# design.net
KiCad netlist of a schematic drawn in Altium Designer
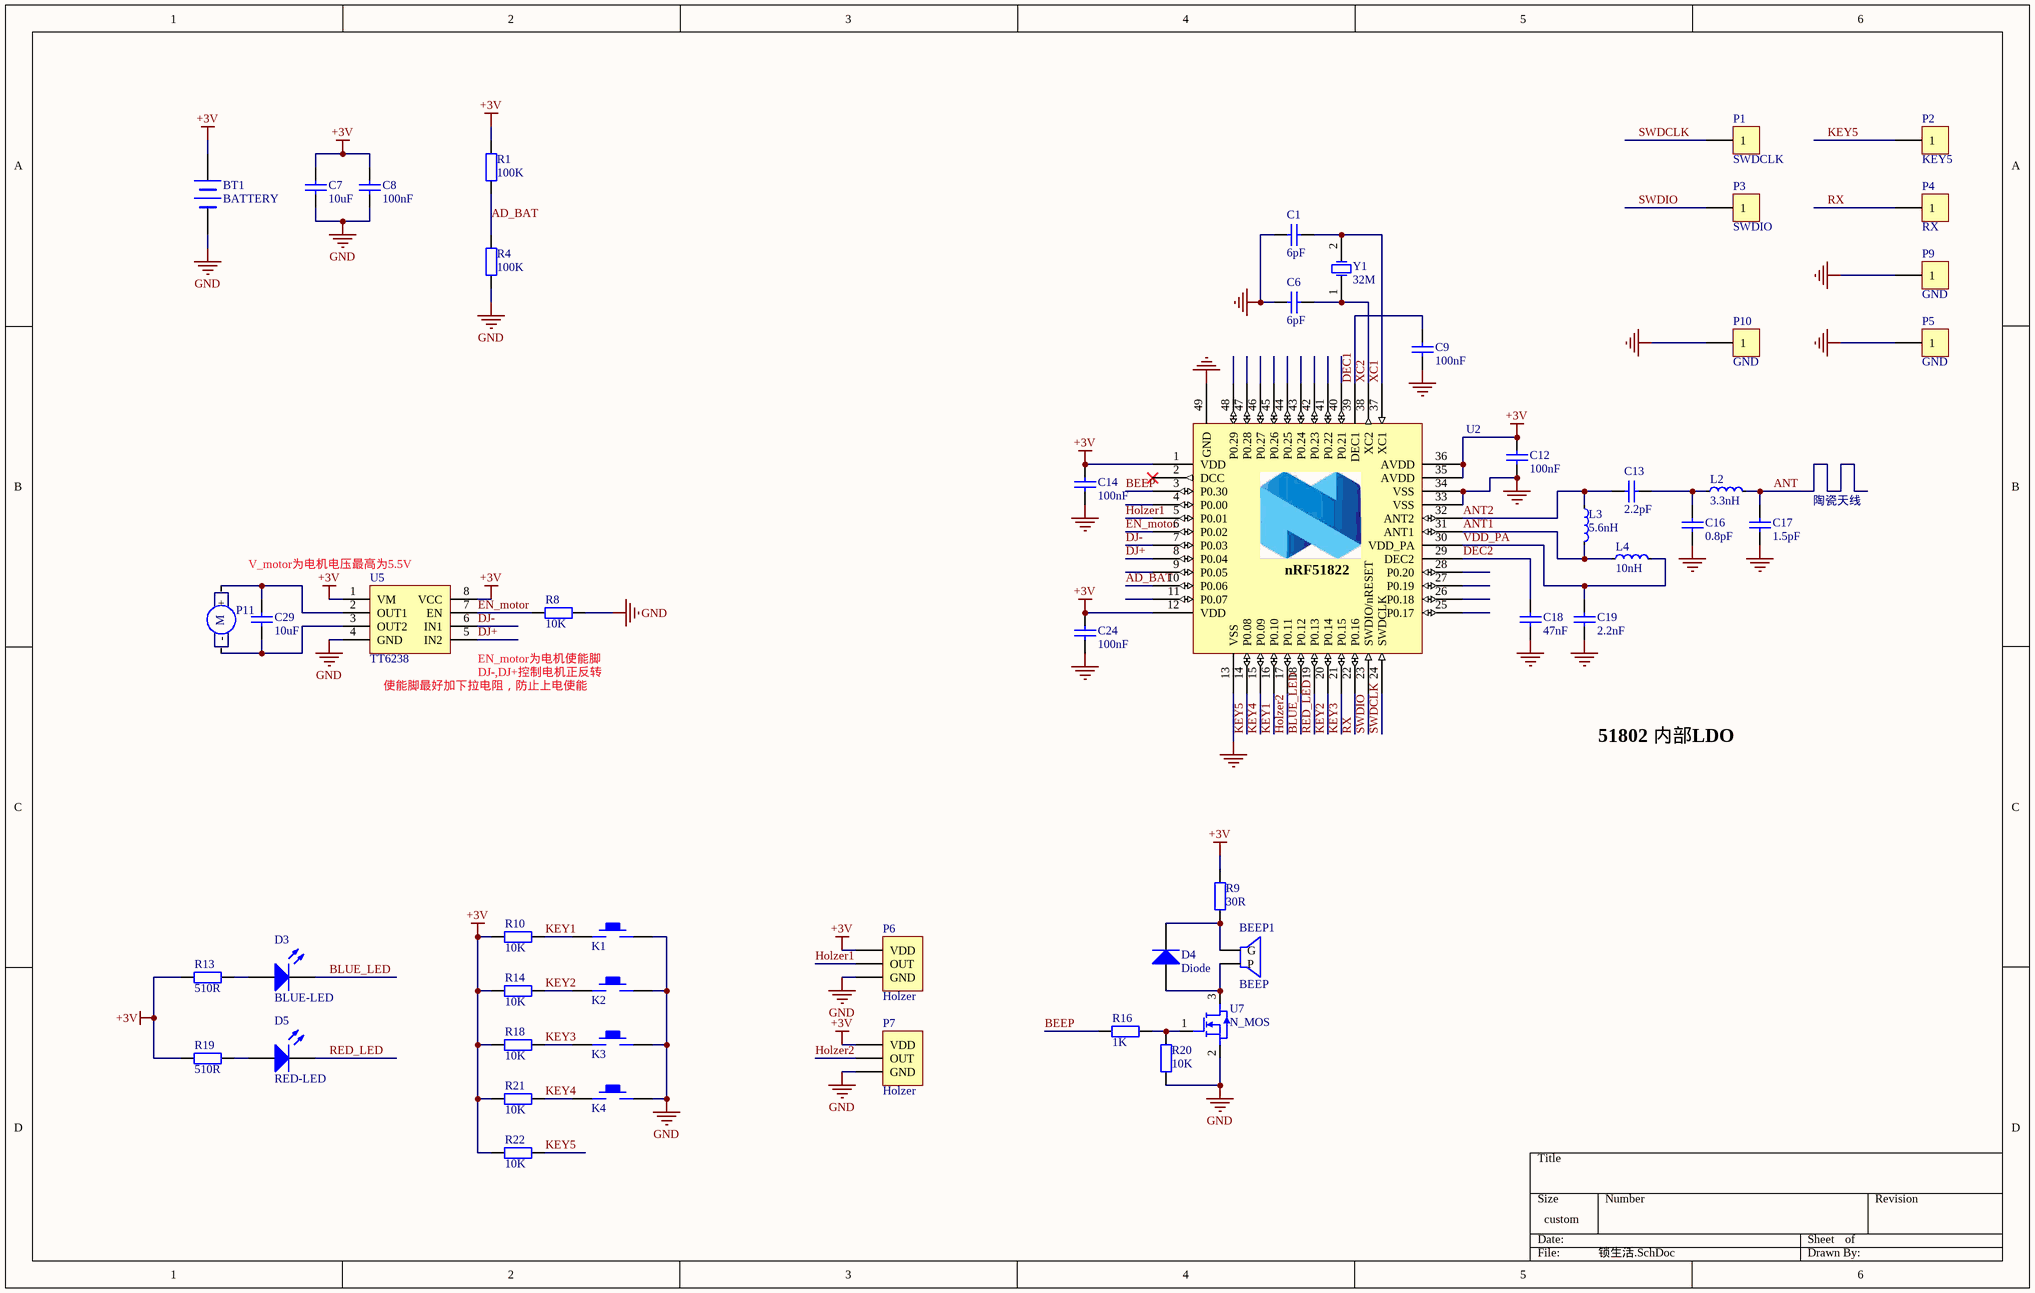
[diagram p0: 锁生活.SchDoc]

(export (version "E")
  (design (tool "Eeschema 10.0.6"))
  (components
    (comp (ref "BEEP1")
      (value "BEEP")
      (footprint "BELL-φ5")
      (description "蜂鸣器")
      (libsource (lib "常用集成库") (part "BEEP"))
    )
    (comp (ref "BT1")
      (value "BATTERY")
      (footprint "2P-1.0卧贴连接器")
      (description "电池")
      (libsource (lib "常用集成库") (part "BATTERY"))
    )
    (comp (ref "C1")
      (value "6pF")
      (footprint "0402_C")
      (description "Capacitor")
      (fields (field (name "PUBLISHER") "Altium Limited"))
      (libsource (lib "常用集成库") (part "Cap"))
    )
    (comp (ref "C6")
      (value "6pF")
      (footprint "0402_C")
      (description "Capacitor")
      (fields (field (name "PUBLISHER") "Altium Limited"))
      (libsource (lib "常用集成库") (part "Cap"))
    )
    (comp (ref "C7")
      (value "10uF")
      (footprint "0402_C")
      (description "Capacitor")
      (fields (field (name "PUBLISHER") "Altium Limited"))
      (libsource (lib "常用集成库") (part "Cap"))
    )
    (comp (ref "C8")
      (value "100nF")
      (footprint "0402_C")
      (description "Capacitor")
      (fields (field (name "PUBLISHER") "Altium Limited"))
      (libsource (lib "常用集成库") (part "Cap"))
    )
    (comp (ref "C9")
      (value "100nF")
      (footprint "0402_C")
      (description "Capacitor")
      (fields (field (name "PUBLISHER") "Altium Limited"))
      (libsource (lib "常用集成库") (part "Cap"))
    )
    (comp (ref "C12")
      (value "100nF")
      (footprint "0402_C")
      (description "Capacitor")
      (fields (field (name "PUBLISHER") "Altium Limited"))
      (libsource (lib "常用集成库") (part "Cap"))
    )
    (comp (ref "C13")
      (value "2.2pF")
      (footprint "0402_C")
      (description "Capacitor")
      (fields (field (name "PUBLISHER") "Altium Limited"))
      (libsource (lib "常用集成库") (part "Cap"))
    )
    (comp (ref "C14")
      (value "100nF")
      (footprint "0402_C")
      (description "Capacitor")
      (fields (field (name "PUBLISHER") "Altium Limited"))
      (libsource (lib "常用集成库") (part "Cap"))
    )
    (comp (ref "C16")
      (value "0.8pF")
      (footprint "0402_C")
      (description "Capacitor")
      (fields (field (name "PUBLISHER") "Altium Limited"))
      (libsource (lib "常用集成库") (part "Cap"))
    )
    (comp (ref "C17")
      (value "1.5pF")
      (footprint "0402_C")
      (description "Capacitor")
      (fields (field (name "PUBLISHER") "Altium Limited"))
      (libsource (lib "常用集成库") (part "Cap"))
    )
    (comp (ref "C18")
      (value "47nF")
      (footprint "0402_C")
      (description "Capacitor")
      (fields (field (name "PUBLISHER") "Altium Limited"))
      (libsource (lib "常用集成库") (part "Cap"))
    )
    (comp (ref "C19")
      (value "2.2nF")
      (footprint "0402_C")
      (description "Capacitor")
      (fields (field (name "PUBLISHER") "Altium Limited"))
      (libsource (lib "常用集成库") (part "Cap"))
    )
    (comp (ref "C24")
      (value "100nF")
      (footprint "0402_C")
      (description "Capacitor")
      (fields (field (name "PUBLISHER") "Altium Limited"))
      (libsource (lib "常用集成库") (part "Cap"))
    )
    (comp (ref "C29")
      (value "10uF")
      (footprint "LC-0402_C")
      (description "Capacitor")
      (fields (field (name "PUBLISHER") "Altium Limited"))
      (libsource (lib "MHLibrary") (part "Cap"))
    )
    (comp (ref "D3")
      (value "BLUE-LED")
      (footprint "0402_LED")
      (description "Typical RED, GREEN, YELLOW, AMBER GaAs LED")
      (fields (field (name "PUBLISHER") "Altium Limited"))
      (libsource (lib "常用集成库") (part "LED"))
    )
    (comp (ref "D4")
      (value "Diode")
      (footprint "SOD-123F")
      (description "diode")
      (fields (field (name "PUBLISHER") "Altium Limited"))
      (libsource (lib "常用集成库") (part "Diode"))
    )
    (comp (ref "D5")
      (value "RED-LED")
      (footprint "0402_LED")
      (description "Typical RED, GREEN, YELLOW, AMBER GaAs LED")
      (fields (field (name "PUBLISHER") "Altium Limited"))
      (libsource (lib "常用集成库") (part "LED"))
    )
    (comp (ref "K1") (value "KEY") (footprint "KEY_SMT4x4x1.5") (libsource (lib "常用集成库") (part "KEY")))
    (comp (ref "K2") (value "KEY") (footprint "KEY_SMT4x4x1.5") (libsource (lib "常用集成库") (part "KEY")))
    (comp (ref "K3") (value "KEY") (footprint "KEY_SMT4x4x1.5") (libsource (lib "常用集成库") (part "KEY")))
    (comp (ref "K4") (value "KEY") (footprint "KEY_SMT4x4x1.5") (libsource (lib "常用集成库") (part "KEY")))
    (comp (ref "L2") (value "3.3nH") (footprint "0402_L") (libsource (lib "常用集成库") (part "L")))
    (comp (ref "L3") (value "5.6nH") (footprint "0402_L") (libsource (lib "常用集成库") (part "L")))
    (comp (ref "L4") (value "10nH") (footprint "0402_L") (libsource (lib "常用集成库") (part "L")))
    (comp (ref "P1")
      (value "SWDCLK")
      (footprint "1P")
      (description "Header, 1-Pin")
      (fields (field (name "PUBLISHER") "Altium Limited"))
      (libsource (lib "常用集成库") (part "Header 1"))
    )
    (comp (ref "P2")
      (value "KEY5")
      (footprint "1P")
      (description "Header, 1-Pin")
      (fields (field (name "PUBLISHER") "Altium Limited"))
      (libsource (lib "常用集成库") (part "Header 1"))
    )
    (comp (ref "P3")
      (value "SWDIO")
      (footprint "1P")
      (description "Header, 1-Pin")
      (fields (field (name "PUBLISHER") "Altium Limited"))
      (libsource (lib "常用集成库") (part "Header 1"))
    )
    (comp (ref "P4")
      (value "RX")
      (footprint "1P")
      (description "Header, 1-Pin")
      (fields (field (name "PUBLISHER") "Altium Limited"))
      (libsource (lib "常用集成库") (part "Header 1"))
    )
    (comp (ref "P5")
      (value "GND")
      (footprint "1P")
      (description "Header, 1-Pin")
      (fields (field (name "PUBLISHER") "Altium Limited"))
      (libsource (lib "常用集成库") (part "Header 1"))
    )
    (comp (ref "P6")
      (value "Holzer")
      (footprint "Holzer")
      (fields (field (name "PUBLISHER") "Altium Limited"))
      (libsource (lib "常用集成库") (part "Holzer"))
    )
    (comp (ref "P7")
      (value "Holzer")
      (footprint "SOT23-3")
      (fields (field (name "PUBLISHER") "Altium Limited"))
      (libsource (lib "常用集成库") (part "Holzer"))
    )
    (comp (ref "P9")
      (value "GND")
      (footprint "1P")
      (description "Header, 1-Pin")
      (fields (field (name "PUBLISHER") "Altium Limited"))
      (libsource (lib "常用集成库") (part "Header 1"))
    )
    (comp (ref "P10")
      (value "GND")
      (footprint "1P")
      (description "Header, 1-Pin")
      (fields (field (name "PUBLISHER") "Altium Limited"))
      (libsource (lib "常用集成库") (part "Header 1"))
    )
    (comp (ref "P11")
      (value "Motor")
      (footprint "2P-1.0卧贴连接器")
      (description "电机")
      (libsource (lib "常用集成库") (part "Motor"))
    )
    (comp (ref "R1")
      (value "100K")
      (footprint "0402_R")
      (description "Resistor")
      (fields (field (name "PUBLISHER") "Altium Limited"))
      (libsource (lib "") (part "Res_2"))
    )
    (comp (ref "R4")
      (value "100K")
      (footprint "0402_R")
      (description "Resistor")
      (fields (field (name "PUBLISHER") "Altium Limited"))
      (libsource (lib "") (part "Res_1"))
    )
    (comp (ref "R8")
      (value "10K")
      (footprint "LC-0402_R")
      (description "Resistor")
      (fields (field (name "PUBLISHER") "Altium Limited"))
      (libsource (lib "MHLibrary") (part "Res"))
    )
    (comp (ref "R9")
      (value "30R")
      (footprint "0402_R")
      (description "Resistor")
      (fields (field (name "PUBLISHER") "Altium Limited"))
      (libsource (lib "") (part "Res_1"))
    )
    (comp (ref "R10")
      (value "10K")
      (footprint "LC-0402_R")
      (description "Resistor")
      (fields (field (name "PUBLISHER") "Altium Limited"))
      (libsource (lib "MHLibrary") (part "Res"))
    )
    (comp (ref "R13")
      (value "510R")
      (footprint "LC-0402_R")
      (description "Resistor")
      (fields (field (name "PUBLISHER") "Altium Limited"))
      (libsource (lib "MHLibrary") (part "Res"))
    )
    (comp (ref "R14")
      (value "10K")
      (footprint "LC-0402_R")
      (description "Resistor")
      (fields (field (name "PUBLISHER") "Altium Limited"))
      (libsource (lib "MHLibrary") (part "Res"))
    )
    (comp (ref "R16")
      (value "1K")
      (footprint "0402_R")
      (description "Resistor")
      (fields (field (name "PUBLISHER") "Altium Limited"))
      (libsource (lib "常用集成库") (part "Res"))
    )
    (comp (ref "R18")
      (value "10K")
      (footprint "LC-0402_R")
      (description "Resistor")
      (fields (field (name "PUBLISHER") "Altium Limited"))
      (libsource (lib "MHLibrary") (part "Res"))
    )
    (comp (ref "R19")
      (value "510R")
      (footprint "LC-0402_R")
      (description "Resistor")
      (fields (field (name "PUBLISHER") "Altium Limited"))
      (libsource (lib "MHLibrary") (part "Res"))
    )
    (comp (ref "R20")
      (value "10K")
      (footprint "0402_R")
      (description "Resistor")
      (fields (field (name "PUBLISHER") "Altium Limited"))
      (libsource (lib "") (part "Res_1"))
    )
    (comp (ref "R21")
      (value "10K")
      (footprint "LC-0402_R")
      (description "Resistor")
      (fields (field (name "PUBLISHER") "Altium Limited"))
      (libsource (lib "MHLibrary") (part "Res"))
    )
    (comp (ref "R22")
      (value "10K")
      (footprint "LC-0402_R")
      (description "Resistor")
      (fields (field (name "PUBLISHER") "Altium Limited"))
      (libsource (lib "") (part "Res_1"))
    )
    (comp (ref "U2")
      (value "nRF51822-QFAA")
      (footprint "QFN-48_6x6x04P")
      (description "Multi-protocol Bluetooth Low Energy and 2.4GHz proprietary system-on-chip")
      (fields
        (field (name "PART NUMBER") "nRF51822-Q48-6x6_DCDC")
        (field (name "MANUFACTURER") "Nordic Semiconductor")
        (field (name "PUBLISHER") "Nordic Semiconductor")
      )
      (libsource (lib "常用集成库") (part "nRF51822_QFN48"))
    )
    (comp (ref "U5") (value "TT6238") (footprint "DFN-8(2*2)") (libsource (lib "MHLibrary") (part "TT6237")))
    (comp (ref "U7") (value "N_MOS") (footprint "SOT23-3") (libsource (lib "常用集成库") (part "N_MOS")))
    (comp (ref "WAN1") (value "陶瓷天线") (footprint "陶瓷天线") (libsource (lib "常用集成库") (part "陶瓷天线")))
    (comp (ref "Y1")
      (value "32M")
      (footprint "XT-2016")
      (description "Crystal Oscillator")
      (fields (field (name "PUBLISHER") "Altium Limited"))
      (libsource (lib "常用集成库") (part "XTAL"))
    )
  )
  (nets
    (net (code "1") (name "+3V") (class "Default")
      (node (ref "BT1") (pin "1") (pinfunction "+_1") (pintype "passive"))
      (node (ref "C12") (pin "2") (pinfunction "2_2") (pintype "passive"))
      (node (ref "C14") (pin "2") (pinfunction "2_2") (pintype "passive"))
      (node (ref "C24") (pin "2") (pinfunction "2_2") (pintype "passive"))
      (node (ref "C7") (pin "2") (pinfunction "2_2") (pintype "passive"))
      (node (ref "C8") (pin "2") (pinfunction "2_2") (pintype "passive"))
      (node (ref "P6") (pin "1") (pinfunction "VDD_1") (pintype "passive"))
      (node (ref "P7") (pin "1") (pinfunction "VDD_1") (pintype "passive"))
      (node (ref "R1") (pin "1") (pinfunction "1_1") (pintype "passive"))
      (node (ref "R10") (pin "1") (pinfunction "1_1") (pintype "passive"))
      (node (ref "R13") (pin "1") (pinfunction "1_1") (pintype "passive"))
      (node (ref "R14") (pin "1") (pinfunction "1_1") (pintype "passive"))
      (node (ref "R18") (pin "1") (pinfunction "1_1") (pintype "passive"))
      (node (ref "R19") (pin "1") (pinfunction "1_1") (pintype "passive"))
      (node (ref "R21") (pin "1") (pinfunction "1_1") (pintype "passive"))
      (node (ref "R22") (pin "2") (pinfunction "2_2") (pintype "passive"))
      (node (ref "R9") (pin "2") (pinfunction "2_2") (pintype "passive"))
      (node (ref "U2") (pin "1") (pinfunction "VDD_1") (pintype "power_in"))
      (node (ref "U2") (pin "12") (pinfunction "VDD_12") (pintype "power_in"))
      (node (ref "U2") (pin "35") (pinfunction "AVDD_35") (pintype "power_in"))
      (node (ref "U2") (pin "36") (pinfunction "AVDD_36") (pintype "power_in"))
      (node (ref "U5") (pin "1") (pinfunction "VM_1") (pintype "passive"))
      (node (ref "U5") (pin "8") (pinfunction "VCC_8") (pintype "passive"))
    )
    (net (code "2") (name "/AD_BAT") (class "Default")
      (node (ref "R1") (pin "2") (pinfunction "2_2") (pintype "passive"))
      (node (ref "R4") (pin "2") (pinfunction "2_2") (pintype "passive"))
      (node (ref "U2") (pin "10") (pinfunction "P0.06_10") (pintype "bidirectional"))
    )
    (net (code "3") (name "/ANT") (class "Default")
      (node (ref "C17") (pin "2") (pinfunction "2_2") (pintype "passive"))
      (node (ref "L2") (pin "2") (pinfunction "2_2") (pintype "passive"))
      (node (ref "WAN1") (pin "1") (pinfunction "1_1") (pintype "passive"))
    )
    (net (code "4") (name "/ANT1") (class "Default")
      (node (ref "L3") (pin "2") (pinfunction "2_2") (pintype "passive"))
      (node (ref "L4") (pin "1") (pinfunction "1_1") (pintype "passive"))
      (node (ref "U2") (pin "31") (pinfunction "ANT1_31") (pintype "bidirectional"))
    )
    (net (code "5") (name "/ANT2") (class "Default")
      (node (ref "C13") (pin "2") (pinfunction "2_2") (pintype "passive"))
      (node (ref "L3") (pin "1") (pinfunction "1_1") (pintype "passive"))
      (node (ref "U2") (pin "32") (pinfunction "ANT2_32") (pintype "bidirectional"))
    )
    (net (code "6") (name "/BEEP") (class "Default")
      (node (ref "R16") (pin "1") (pinfunction "1_1") (pintype "passive"))
      (node (ref "U2") (pin "3") (pinfunction "P0.30_3") (pintype "bidirectional"))
    )
    (net (code "7") (name "/BLUE_LED") (class "Default")
      (node (ref "D3") (pin "K") (pinfunction "K_K") (pintype "passive"))
      (node (ref "U2") (pin "18") (pinfunction "P0.12_18") (pintype "bidirectional"))
    )
    (net (code "8") (name "/DEC1") (class "Default")
      (node (ref "C9") (pin "2") (pinfunction "2_2") (pintype "passive"))
      (node (ref "U2") (pin "39") (pinfunction "DEC1_39") (pintype "power_in"))
    )
    (net (code "9") (name "/DEC2") (class "Default")
      (node (ref "C18") (pin "2") (pinfunction "2_2") (pintype "passive"))
      (node (ref "U2") (pin "29") (pinfunction "DEC2_29") (pintype "power_in"))
    )
    (net (code "10") (name "/DJ+") (class "Default")
      (node (ref "U2") (pin "8") (pinfunction "P0.04_8") (pintype "bidirectional"))
      (node (ref "U5") (pin "5") (pinfunction "IN2_5") (pintype "passive"))
    )
    (net (code "11") (name "/DJ-") (class "Default")
      (node (ref "U2") (pin "7") (pinfunction "P0.03_7") (pintype "bidirectional"))
      (node (ref "U5") (pin "6") (pinfunction "IN1_6") (pintype "passive"))
    )
    (net (code "12") (name "/EN_motor") (class "Default")
      (node (ref "R8") (pin "1") (pinfunction "1_1") (pintype "passive"))
      (node (ref "U2") (pin "6") (pinfunction "P0.02_6") (pintype "bidirectional"))
      (node (ref "U5") (pin "7") (pinfunction "EN_7") (pintype "passive"))
    )
    (net (code "13") (name "/Holzer1") (class "Default")
      (node (ref "P6") (pin "2") (pinfunction "OUT_2") (pintype "passive"))
      (node (ref "U2") (pin "5") (pinfunction "P0.01_5") (pintype "bidirectional"))
    )
    (net (code "14") (name "/Holzer2") (class "Default")
      (node (ref "P7") (pin "2") (pinfunction "OUT_2") (pintype "passive"))
      (node (ref "U2") (pin "17") (pinfunction "P0.11_17") (pintype "bidirectional"))
    )
    (net (code "15") (name "/KEY1") (class "Default")
      (node (ref "K1") (pin "1") (pinfunction "1_1") (pintype "passive"))
      (node (ref "R10") (pin "2") (pinfunction "2_2") (pintype "passive"))
      (node (ref "U2") (pin "16") (pinfunction "P0.10_16") (pintype "bidirectional"))
    )
    (net (code "16") (name "/KEY2") (class "Default")
      (node (ref "K2") (pin "1") (pinfunction "1_1") (pintype "passive"))
      (node (ref "R14") (pin "2") (pinfunction "2_2") (pintype "passive"))
      (node (ref "U2") (pin "20") (pinfunction "P0.14_20") (pintype "bidirectional"))
    )
    (net (code "17") (name "/KEY3") (class "Default")
      (node (ref "K3") (pin "1") (pinfunction "1_1") (pintype "passive"))
      (node (ref "R18") (pin "2") (pinfunction "2_2") (pintype "passive"))
      (node (ref "U2") (pin "21") (pinfunction "P0.15_21") (pintype "bidirectional"))
    )
    (net (code "18") (name "/KEY4") (class "Default")
      (node (ref "K4") (pin "1") (pinfunction "1_1") (pintype "passive"))
      (node (ref "R21") (pin "2") (pinfunction "2_2") (pintype "passive"))
      (node (ref "U2") (pin "15") (pinfunction "P0.09_15") (pintype "bidirectional"))
    )
    (net (code "19") (name "/KEY5") (class "Default")
      (node (ref "P2") (pin "1") (pinfunction "1_1") (pintype "passive"))
      (node (ref "R22") (pin "1") (pinfunction "1_1") (pintype "passive"))
      (node (ref "U2") (pin "14") (pinfunction "P0.08_14") (pintype "bidirectional"))
    )
    (net (code "20") (name "/RED_LED") (class "Default")
      (node (ref "D5") (pin "K") (pinfunction "K_K") (pintype "passive"))
      (node (ref "U2") (pin "19") (pinfunction "P0.13_19") (pintype "bidirectional"))
    )
    (net (code "21") (name "/RX") (class "Default")
      (node (ref "P4") (pin "1") (pinfunction "1_1") (pintype "passive"))
      (node (ref "U2") (pin "22") (pinfunction "P0.16_22") (pintype "bidirectional"))
    )
    (net (code "22") (name "/SWDCLK") (class "Default")
      (node (ref "P1") (pin "1") (pinfunction "1_1") (pintype "passive"))
      (node (ref "U2") (pin "24") (pinfunction "SWDCLK_24") (pintype "input"))
    )
    (net (code "23") (name "/SWDIO") (class "Default")
      (node (ref "P3") (pin "1") (pinfunction "1_1") (pintype "passive"))
      (node (ref "U2") (pin "23") (pinfunction "SWDIO/nRESET_23") (pintype "input"))
    )
    (net (code "24") (name "/VDD_PA") (class "Default")
      (node (ref "C19") (pin "2") (pinfunction "2_2") (pintype "passive"))
      (node (ref "L4") (pin "2") (pinfunction "2_2") (pintype "passive"))
      (node (ref "U2") (pin "30") (pinfunction "VDD_PA_30") (pintype "power_in"))
    )
    (net (code "25") (name "/XC1") (class "Default")
      (node (ref "C1") (pin "2") (pinfunction "2_2") (pintype "passive"))
      (node (ref "U2") (pin "37") (pinfunction "XC1_37") (pintype "input"))
      (node (ref "Y1") (pin "2") (pinfunction "OSC2_2") (pintype "passive"))
    )
    (net (code "26") (name "/XC2") (class "Default")
      (node (ref "C6") (pin "2") (pinfunction "2_2") (pintype "passive"))
      (node (ref "U2") (pin "38") (pinfunction "XC2_38") (pintype "output"))
      (node (ref "Y1") (pin "1") (pinfunction "OSC1_1") (pintype "passive"))
    )
    (net (code "27") (name "49") (class "Default")
      (node (ref "U2") (pin "49") (pinfunction "49_49") (pintype "power_in"))
    )
    (net (code "28") (name "GND") (class "Default")
      (node (ref "BT1") (pin "2") (pinfunction "-_2") (pintype "passive"))
      (node (ref "C1") (pin "1") (pinfunction "1_1") (pintype "passive"))
      (node (ref "C12") (pin "1") (pinfunction "1_1") (pintype "passive"))
      (node (ref "C14") (pin "1") (pinfunction "1_1") (pintype "passive"))
      (node (ref "C16") (pin "1") (pinfunction "1_1") (pintype "passive"))
      (node (ref "C17") (pin "1") (pinfunction "1_1") (pintype "passive"))
      (node (ref "C18") (pin "1") (pinfunction "1_1") (pintype "passive"))
      (node (ref "C19") (pin "1") (pinfunction "1_1") (pintype "passive"))
      (node (ref "C24") (pin "1") (pinfunction "1_1") (pintype "passive"))
      (node (ref "C6") (pin "1") (pinfunction "1_1") (pintype "passive"))
      (node (ref "C7") (pin "1") (pinfunction "1_1") (pintype "passive"))
      (node (ref "C8") (pin "1") (pinfunction "1_1") (pintype "passive"))
      (node (ref "C9") (pin "1") (pinfunction "1_1") (pintype "passive"))
      (node (ref "K1") (pin "2") (pinfunction "2_2") (pintype "passive"))
      (node (ref "K2") (pin "2") (pinfunction "2_2") (pintype "passive"))
      (node (ref "K3") (pin "2") (pinfunction "2_2") (pintype "passive"))
      (node (ref "K4") (pin "2") (pinfunction "2_2") (pintype "passive"))
      (node (ref "P10") (pin "1") (pinfunction "1_1") (pintype "passive"))
      (node (ref "P5") (pin "1") (pinfunction "1_1") (pintype "passive"))
      (node (ref "P6") (pin "3") (pinfunction "GND_3") (pintype "passive"))
      (node (ref "P7") (pin "3") (pinfunction "GND_3") (pintype "passive"))
      (node (ref "P9") (pin "1") (pinfunction "1_1") (pintype "passive"))
      (node (ref "R20") (pin "1") (pinfunction "1_1") (pintype "passive"))
      (node (ref "R4") (pin "1") (pinfunction "1_1") (pintype "passive"))
      (node (ref "R8") (pin "2") (pinfunction "2_2") (pintype "passive"))
      (node (ref "U2") (pin "13") (pinfunction "VSS_13") (pintype "power_in"))
      (node (ref "U2") (pin "33") (pinfunction "VSS_33") (pintype "power_in"))
      (node (ref "U2") (pin "34") (pinfunction "VSS_34") (pintype "power_in"))
      (node (ref "U2") (pin "49") (pinfunction "GND_49") (pintype "passive"))
      (node (ref "U5") (pin "4") (pinfunction "GND_4") (pintype "passive"))
      (node (ref "U7") (pin "2") (pinfunction "S_2") (pintype "passive"))
    )
    (net (code "29") (name "Net-(BEEP1-G)") (class "Default")
      (node (ref "BEEP1") (pin "2") (pinfunction "G_2") (pintype "passive"))
      (node (ref "D4") (pin "1") (pinfunction "K_1") (pintype "passive"))
      (node (ref "R9") (pin "1") (pinfunction "1_1") (pintype "passive"))
    )
    (net (code "30") (name "Net-(BEEP1-P)") (class "Default")
      (node (ref "BEEP1") (pin "1") (pinfunction "P_1") (pintype "passive"))
      (node (ref "D4") (pin "2") (pinfunction "A_2") (pintype "passive"))
      (node (ref "U7") (pin "3") (pinfunction "D_3") (pintype "passive"))
    )
    (net (code "31") (name "Net-(C13-Pad1)") (class "Default")
      (node (ref "C13") (pin "1") (pinfunction "1_1") (pintype "passive"))
      (node (ref "C16") (pin "2") (pinfunction "2_2") (pintype "passive"))
      (node (ref "L2") (pin "1") (pinfunction "1_1") (pintype "passive"))
    )
    (net (code "32") (name "Net-(D3-PadA)") (class "Default")
      (node (ref "D3") (pin "A") (pinfunction "A_A") (pintype "passive"))
      (node (ref "R13") (pin "2") (pinfunction "2_2") (pintype "passive"))
    )
    (net (code "33") (name "Net-(D5-PadA)") (class "Default")
      (node (ref "D5") (pin "A") (pinfunction "A_A") (pintype "passive"))
      (node (ref "R19") (pin "2") (pinfunction "2_2") (pintype "passive"))
    )
    (net (code "34") (name "Net-(P11-+)") (class "Default")
      (node (ref "C29") (pin "2") (pinfunction "2_2") (pintype "passive"))
      (node (ref "P11") (pin "1") (pinfunction "+_1") (pintype "passive"))
      (node (ref "U5") (pin "2") (pinfunction "OUT1_2") (pintype "passive"))
    )
    (net (code "35") (name "Net-(P11--)") (class "Default")
      (node (ref "C29") (pin "1") (pinfunction "1_1") (pintype "passive"))
      (node (ref "P11") (pin "2") (pinfunction "-_2") (pintype "passive"))
      (node (ref "U5") (pin "3") (pinfunction "OUT2_3") (pintype "passive"))
    )
    (net (code "36") (name "Net-(U7-G)") (class "Default")
      (node (ref "R16") (pin "2") (pinfunction "2_2") (pintype "passive"))
      (node (ref "R20") (pin "2") (pinfunction "2_2") (pintype "passive"))
      (node (ref "U7") (pin "1") (pinfunction "G_1") (pintype "passive"))
    )
    (net (code "37") (name "unconnected-(U2-DCC-Pad2)") (class "Default")
      (node (ref "U2") (pin "2") (pinfunction "DCC_2") (pintype "output+no_connect"))
    )
    (net (code "38") (name "unconnected-(U2-P0.00-Pad4)") (class "Default")
      (node (ref "U2") (pin "4") (pinfunction "P0.00_4") (pintype "bidirectional"))
    )
    (net (code "39") (name "unconnected-(U2-P0.05-Pad9)") (class "Default")
      (node (ref "U2") (pin "9") (pinfunction "P0.05_9") (pintype "bidirectional"))
    )
    (net (code "40") (name "unconnected-(U2-P0.07-Pad11)") (class "Default")
      (node (ref "U2") (pin "11") (pinfunction "P0.07_11") (pintype "bidirectional"))
    )
    (net (code "41") (name "unconnected-(U2-P0.17-Pad25)") (class "Default")
      (node (ref "U2") (pin "25") (pinfunction "P0.17_25") (pintype "bidirectional"))
    )
    (net (code "42") (name "unconnected-(U2-P0.18-Pad26)") (class "Default")
      (node (ref "U2") (pin "26") (pinfunction "P0.18_26") (pintype "bidirectional"))
    )
    (net (code "43") (name "unconnected-(U2-P0.19-Pad27)") (class "Default")
      (node (ref "U2") (pin "27") (pinfunction "P0.19_27") (pintype "bidirectional"))
    )
    (net (code "44") (name "unconnected-(U2-P0.20-Pad28)") (class "Default")
      (node (ref "U2") (pin "28") (pinfunction "P0.20_28") (pintype "bidirectional"))
    )
    (net (code "45") (name "unconnected-(U2-P0.21-Pad40)") (class "Default")
      (node (ref "U2") (pin "40") (pinfunction "P0.21_40") (pintype "bidirectional"))
    )
    (net (code "46") (name "unconnected-(U2-P0.22-Pad41)") (class "Default")
      (node (ref "U2") (pin "41") (pinfunction "P0.22_41") (pintype "bidirectional"))
    )
    (net (code "47") (name "unconnected-(U2-P0.23-Pad42)") (class "Default")
      (node (ref "U2") (pin "42") (pinfunction "P0.23_42") (pintype "bidirectional"))
    )
    (net (code "48") (name "unconnected-(U2-P0.24-Pad43)") (class "Default")
      (node (ref "U2") (pin "43") (pinfunction "P0.24_43") (pintype "bidirectional"))
    )
    (net (code "49") (name "unconnected-(U2-P0.25-Pad44)") (class "Default")
      (node (ref "U2") (pin "44") (pinfunction "P0.25_44") (pintype "bidirectional"))
    )
    (net (code "50") (name "unconnected-(U2-P0.26-Pad45)") (class "Default")
      (node (ref "U2") (pin "45") (pinfunction "P0.26_45") (pintype "bidirectional"))
    )
    (net (code "51") (name "unconnected-(U2-P0.27-Pad46)") (class "Default")
      (node (ref "U2") (pin "46") (pinfunction "P0.27_46") (pintype "bidirectional"))
    )
    (net (code "52") (name "unconnected-(U2-P0.28-Pad47)") (class "Default")
      (node (ref "U2") (pin "47") (pinfunction "P0.28_47") (pintype "bidirectional"))
    )
    (net (code "53") (name "unconnected-(U2-P0.29-Pad48)") (class "Default")
      (node (ref "U2") (pin "48") (pinfunction "P0.29_48") (pintype "bidirectional"))
    )
    (net (code "54") (name "unconnected-(WAN1-Pad2)") (class "Default")
      (node (ref "WAN1") (pin "2") (pinfunction "2_2") (pintype "passive"))
    )
  )
)
